# WanderDrive_AbsEnc.net
KiCad netlist of a schematic drawn in Altium Designer
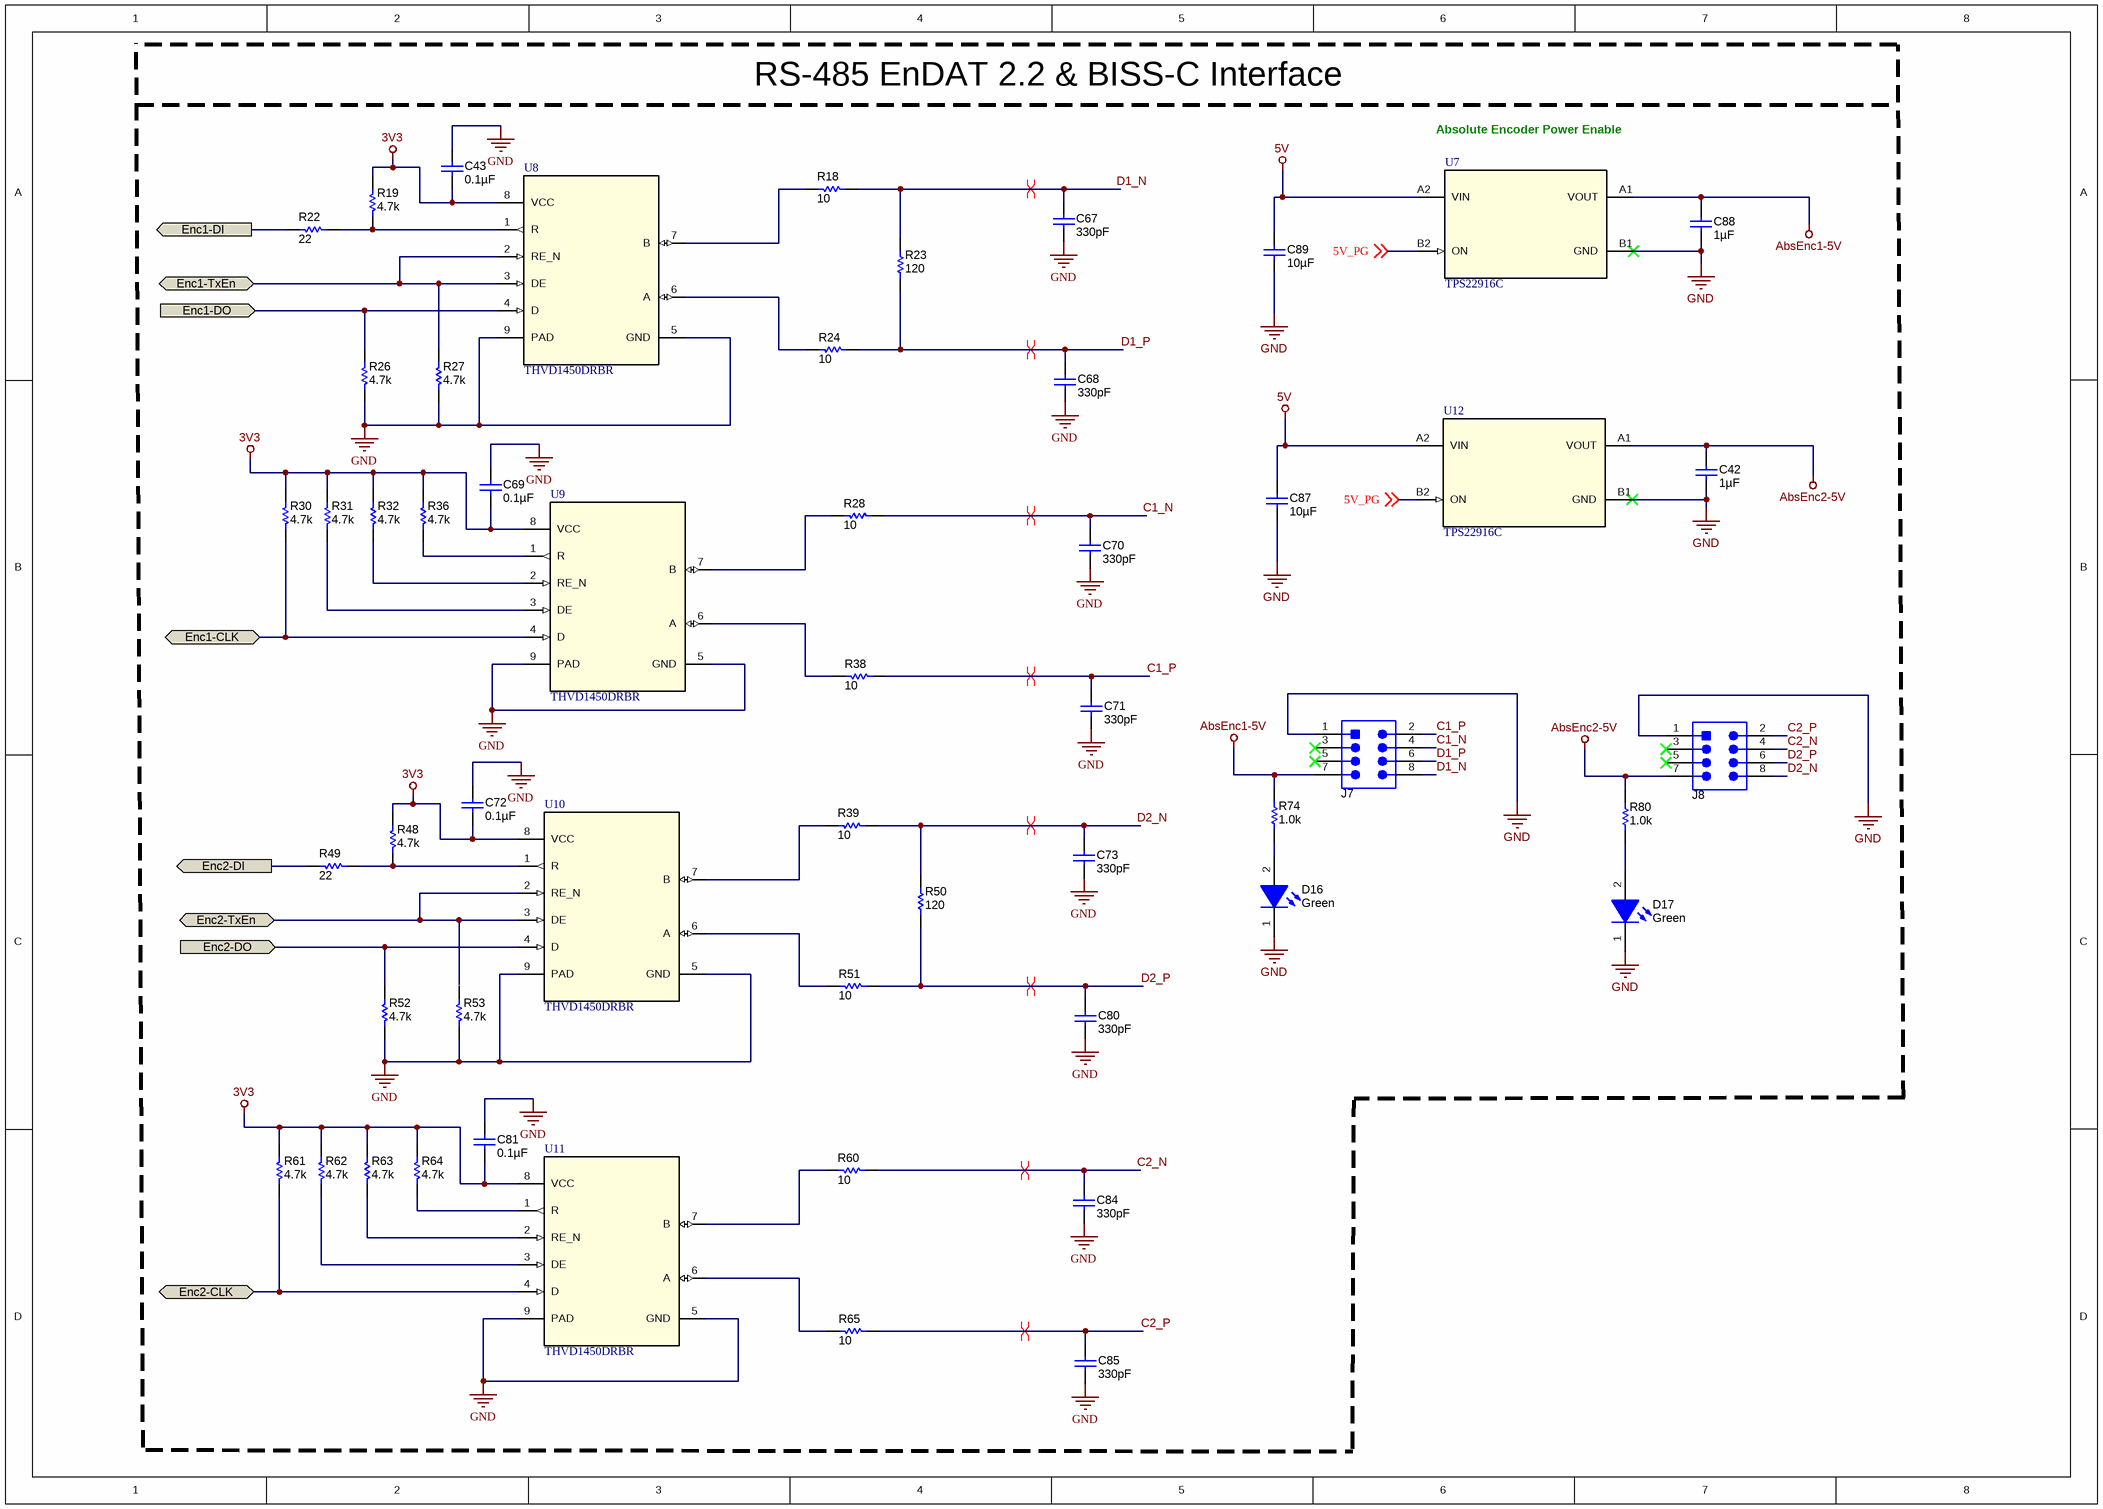
[diagram p0: WanderDrive_AbsEnc.SchDoc]

(export (version "E")
  (design (tool "Eeschema 10.0.6"))
  (components
    (comp (ref "C42")
      (value "TMK212BJ105KG-T")
      (footprint "0805_HV")
      (description "CAP, CERM, 1 µF, 20 V, +/- 10%, X5R, 0805")
      (fields
        (field (name "VALUEDISPLAYED") "1µF")
        (field (name "MANUFACTURER") "Taiyo Yuden")
        (field (name "PUBLISHER") "Texas Instruments")
      )
      (libsource (lib "Capacitor_Ceramic") (part "TMK212BJ105KG-T"))
    )
    (comp (ref "C43")
      (value "06033D104KAT2A")
      (footprint "0603")
      (description "CAP, CERM, 0.1uF, 25V, +/-10%, X5R, 0603")
      (fields
        (field (name "VALUEDISPLAYED") "0.1µF")
        (field (name "MANUFACTURER") "AVX")
        (field (name "PUBLISHER") "Texas Instruments")
      )
      (libsource (lib "Capacitor_Ceramic") (part "06033D104KAT2A"))
    )
    (comp (ref "C67")
      (value "GRM188R71H331KA01D")
      (footprint "0603")
      (description "CAP, CERM, 330pF, 50V, +/-10%, X7R, 0603")
      (fields
        (field (name "VALUEDISPLAYED") "330pF")
        (field (name "MANUFACTURER") "MuRata")
        (field (name "PUBLISHER") "Texas Instruments")
      )
      (libsource (lib "Capacitor_Ceramic") (part "GRM188R71H331KA01D"))
    )
    (comp (ref "C68")
      (value "GRM188R71H331KA01D")
      (footprint "0603")
      (description "CAP, CERM, 330pF, 50V, +/-10%, X7R, 0603")
      (fields
        (field (name "VALUEDISPLAYED") "330pF")
        (field (name "MANUFACTURER") "MuRata")
        (field (name "PUBLISHER") "Texas Instruments")
      )
      (libsource (lib "Capacitor_Ceramic") (part "GRM188R71H331KA01D"))
    )
    (comp (ref "C69")
      (value "06033D104KAT2A")
      (footprint "0603")
      (description "CAP, CERM, 0.1uF, 25V, +/-10%, X5R, 0603")
      (fields
        (field (name "VALUEDISPLAYED") "0.1µF")
        (field (name "MANUFACTURER") "AVX")
        (field (name "PUBLISHER") "Texas Instruments")
      )
      (libsource (lib "Capacitor_Ceramic") (part "06033D104KAT2A"))
    )
    (comp (ref "C70")
      (value "GRM188R71H331KA01D")
      (footprint "0603")
      (description "CAP, CERM, 330pF, 50V, +/-10%, X7R, 0603")
      (fields
        (field (name "VALUEDISPLAYED") "330pF")
        (field (name "MANUFACTURER") "MuRata")
        (field (name "PUBLISHER") "Texas Instruments")
      )
      (libsource (lib "Capacitor_Ceramic") (part "GRM188R71H331KA01D"))
    )
    (comp (ref "C71")
      (value "GRM188R71H331KA01D")
      (footprint "0603")
      (description "CAP, CERM, 330pF, 50V, +/-10%, X7R, 0603")
      (fields
        (field (name "VALUEDISPLAYED") "330pF")
        (field (name "MANUFACTURER") "MuRata")
        (field (name "PUBLISHER") "Texas Instruments")
      )
      (libsource (lib "Capacitor_Ceramic") (part "GRM188R71H331KA01D"))
    )
    (comp (ref "C72")
      (value "06033D104KAT2A")
      (footprint "0603")
      (description "CAP, CERM, 0.1uF, 25V, +/-10%, X5R, 0603")
      (fields
        (field (name "VALUEDISPLAYED") "0.1µF")
        (field (name "MANUFACTURER") "AVX")
        (field (name "PUBLISHER") "Texas Instruments")
      )
      (libsource (lib "Capacitor_Ceramic") (part "06033D104KAT2A"))
    )
    (comp (ref "C73")
      (value "GRM188R71H331KA01D")
      (footprint "0603")
      (description "CAP, CERM, 330pF, 50V, +/-10%, X7R, 0603")
      (fields
        (field (name "VALUEDISPLAYED") "330pF")
        (field (name "MANUFACTURER") "MuRata")
        (field (name "PUBLISHER") "Texas Instruments")
      )
      (libsource (lib "Capacitor_Ceramic") (part "GRM188R71H331KA01D"))
    )
    (comp (ref "C80")
      (value "GRM188R71H331KA01D")
      (footprint "0603")
      (description "CAP, CERM, 330pF, 50V, +/-10%, X7R, 0603")
      (fields
        (field (name "VALUEDISPLAYED") "330pF")
        (field (name "MANUFACTURER") "MuRata")
        (field (name "PUBLISHER") "Texas Instruments")
      )
      (libsource (lib "Capacitor_Ceramic") (part "GRM188R71H331KA01D"))
    )
    (comp (ref "C81")
      (value "06033D104KAT2A")
      (footprint "0603")
      (description "CAP, CERM, 0.1uF, 25V, +/-10%, X5R, 0603")
      (fields
        (field (name "VALUEDISPLAYED") "0.1µF")
        (field (name "MANUFACTURER") "AVX")
        (field (name "PUBLISHER") "Texas Instruments")
      )
      (libsource (lib "Capacitor_Ceramic") (part "06033D104KAT2A"))
    )
    (comp (ref "C84")
      (value "GRM188R71H331KA01D")
      (footprint "0603")
      (description "CAP, CERM, 330pF, 50V, +/-10%, X7R, 0603")
      (fields
        (field (name "VALUEDISPLAYED") "330pF")
        (field (name "MANUFACTURER") "MuRata")
        (field (name "PUBLISHER") "Texas Instruments")
      )
      (libsource (lib "Capacitor_Ceramic") (part "GRM188R71H331KA01D"))
    )
    (comp (ref "C85")
      (value "GRM188R71H331KA01D")
      (footprint "0603")
      (description "CAP, CERM, 330pF, 50V, +/-10%, X7R, 0603")
      (fields
        (field (name "VALUEDISPLAYED") "330pF")
        (field (name "MANUFACTURER") "MuRata")
        (field (name "PUBLISHER") "Texas Instruments")
      )
      (libsource (lib "Capacitor_Ceramic") (part "GRM188R71H331KA01D"))
    )
    (comp (ref "C87")
      (value "GRM21BR61E106KA73L")
      (footprint "0805_HV")
      (description "CAP, CERM, 10 µF, 25 V,+/- 10%, X5R, 0805")
      (fields
        (field (name "VALUEDISPLAYED") "10µF")
        (field (name "MANUFACTURER") "MuRata")
        (field (name "PUBLISHER") "Texas Instruments")
      )
      (libsource (lib "Capacitor_Ceramic") (part "GRM21BR61E106KA73L"))
    )
    (comp (ref "C88")
      (value "TMK212BJ105KG-T")
      (footprint "0805_HV")
      (description "CAP, CERM, 1 µF, 20 V, +/- 10%, X5R, 0805")
      (fields
        (field (name "VALUEDISPLAYED") "1µF")
        (field (name "MANUFACTURER") "Taiyo Yuden")
        (field (name "PUBLISHER") "Texas Instruments")
      )
      (libsource (lib "Capacitor_Ceramic") (part "TMK212BJ105KG-T"))
    )
    (comp (ref "C89")
      (value "GRM21BR61E106KA73L")
      (footprint "0805_HV")
      (description "CAP, CERM, 10 µF, 25 V,+/- 10%, X5R, 0805")
      (fields
        (field (name "VALUEDISPLAYED") "10µF")
        (field (name "MANUFACTURER") "MuRata")
        (field (name "PUBLISHER") "Texas Instruments")
      )
      (libsource (lib "Capacitor_Ceramic") (part "GRM21BR61E106KA73L"))
    )
    (comp (ref "D16")
      (value "Green")
      (footprint "WL-SMCW_GREEN")
      (description "LED, Green, SMD")
      (fields
        (field (name "MANUFACTURER") "Wurth Elektronik")
        (field (name "PARTNUMBER") "150060GS75000")
        (field (name "PUBLISHER") "Texas Instruments")
      )
      (libsource (lib "LED") (part "150060GS75000"))
    )
    (comp (ref "D17")
      (value "Green")
      (footprint "WL-SMCW_GREEN")
      (description "LED, Green, SMD")
      (fields
        (field (name "MANUFACTURER") "Wurth Elektronik")
        (field (name "PARTNUMBER") "150060GS75000")
        (field (name "PUBLISHER") "Texas Instruments")
      )
      (libsource (lib "LED") (part "150060GS75000"))
    )
    (comp (ref "J7")
      (value "70246-0801")
      (footprint "Molex_70246-0801")
      (description "Header(shrouded), 2.54mm, 4x2, Gold, TH")
      (fields
        (field (name "MANUFACTURER") "Molex")
        (field (name "SYMBOLCREATOR") "a0411947")
        (field (name "PUBLISHER") "Texas Instruments")
      )
      (libsource (lib "Connectors_Molex") (part "70246-0801"))
    )
    (comp (ref "J8")
      (value "70246-0801")
      (footprint "Molex_70246-0801")
      (description "Header(shrouded), 2.54mm, 4x2, Gold, TH")
      (fields
        (field (name "MANUFACTURER") "Molex")
        (field (name "SYMBOLCREATOR") "a0411947")
        (field (name "PUBLISHER") "Texas Instruments")
      )
      (libsource (lib "Connectors_Molex") (part "70246-0801"))
    )
    (comp (ref "R18")
      (value "10")
      (footprint "0603")
      (description "RES, 10 ohm, 5%, 0.25W, 0603")
      (fields
        (field (name "PARTNUMBER") "CRCW060310R0JNEAHP")
        (field (name "MANUFACTURER") "Vishay-Dale")
        (field (name "PUBLISHER") "Texas Instruments")
      )
      (libsource (lib "Resistor_0603") (part "CRCW060310R0JNEAHP"))
    )
    (comp (ref "R19")
      (value "4.7k")
      (footprint "0603")
      (description "RES, 4.7k ohm, 5%, 0.1W, 0603")
      (fields
        (field (name "PARTNUMBER") "CRCW06034K70JNEA")
        (field (name "MANUFACTURER") "Vishay-Dale")
        (field (name "PUBLISHER") "Texas Instruments")
      )
      (libsource (lib "Resistor_0603") (part "CRCW06034K70JNEA"))
    )
    (comp (ref "R22")
      (value "22")
      (footprint "0603")
      (description "RES, 22 ohm, 5%, 0.1W, 0603")
      (fields
        (field (name "PARTNUMBER") "CRCW060322R0JNEA")
        (field (name "MANUFACTURER") "Vishay-Dale")
        (field (name "PUBLISHER") "Texas Instruments")
      )
      (libsource (lib "Resistor_0603") (part "CRCW060322R0JNEA"))
    )
    (comp (ref "R23")
      (value "CRCW0603120RJNEA")
      (footprint "0603")
      (description "RES, 120, 5%, 0.1 W, 0603")
      (fields
        (field (name "VALUEDISPLAYED") "120")
        (field (name "MANUFACTURER") "Vishay-Dale")
        (field (name "PUBLISHER") "Texas Instruments")
      )
      (libsource (lib "Resistor_0603") (part "CRCW0603120RJNEA"))
    )
    (comp (ref "R24")
      (value "10")
      (footprint "0603")
      (description "RES, 10 ohm, 5%, 0.25W, 0603")
      (fields
        (field (name "PARTNUMBER") "CRCW060310R0JNEAHP")
        (field (name "MANUFACTURER") "Vishay-Dale")
        (field (name "PUBLISHER") "Texas Instruments")
      )
      (libsource (lib "Resistor_0603") (part "CRCW060310R0JNEAHP"))
    )
    (comp (ref "R26")
      (value "4.7k")
      (footprint "0603")
      (description "RES, 4.7k ohm, 5%, 0.1W, 0603")
      (fields
        (field (name "PARTNUMBER") "CRCW06034K70JNEA")
        (field (name "MANUFACTURER") "Vishay-Dale")
        (field (name "PUBLISHER") "Texas Instruments")
      )
      (libsource (lib "Resistor_0603") (part "CRCW06034K70JNEA"))
    )
    (comp (ref "R27")
      (value "4.7k")
      (footprint "0603")
      (description "RES, 4.7k ohm, 5%, 0.1W, 0603")
      (fields
        (field (name "PARTNUMBER") "CRCW06034K70JNEA")
        (field (name "MANUFACTURER") "Vishay-Dale")
        (field (name "PUBLISHER") "Texas Instruments")
      )
      (libsource (lib "Resistor_0603") (part "CRCW06034K70JNEA"))
    )
    (comp (ref "R28")
      (value "10")
      (footprint "0603")
      (description "RES, 10 ohm, 5%, 0.25W, 0603")
      (fields
        (field (name "PARTNUMBER") "CRCW060310R0JNEAHP")
        (field (name "MANUFACTURER") "Vishay-Dale")
        (field (name "PUBLISHER") "Texas Instruments")
      )
      (libsource (lib "Resistor_0603") (part "CRCW060310R0JNEAHP"))
    )
    (comp (ref "R30")
      (value "4.7k")
      (footprint "0603")
      (description "RES, 4.7k ohm, 5%, 0.1W, 0603")
      (fields
        (field (name "PARTNUMBER") "CRCW06034K70JNEA")
        (field (name "MANUFACTURER") "Vishay-Dale")
        (field (name "PUBLISHER") "Texas Instruments")
      )
      (libsource (lib "Resistor_0603") (part "CRCW06034K70JNEA"))
    )
    (comp (ref "R31")
      (value "4.7k")
      (footprint "0603")
      (description "RES, 4.7k ohm, 5%, 0.1W, 0603")
      (fields
        (field (name "PARTNUMBER") "CRCW06034K70JNEA")
        (field (name "MANUFACTURER") "Vishay-Dale")
        (field (name "PUBLISHER") "Texas Instruments")
      )
      (libsource (lib "Resistor_0603") (part "CRCW06034K70JNEA"))
    )
    (comp (ref "R32")
      (value "4.7k")
      (footprint "0603")
      (description "RES, 4.7k ohm, 5%, 0.1W, 0603")
      (fields
        (field (name "PARTNUMBER") "CRCW06034K70JNEA")
        (field (name "MANUFACTURER") "Vishay-Dale")
        (field (name "PUBLISHER") "Texas Instruments")
      )
      (libsource (lib "Resistor_0603") (part "CRCW06034K70JNEA"))
    )
    (comp (ref "R36")
      (value "4.7k")
      (footprint "0603")
      (description "RES, 4.7k ohm, 5%, 0.1W, 0603")
      (fields
        (field (name "PARTNUMBER") "CRCW06034K70JNEA")
        (field (name "MANUFACTURER") "Vishay-Dale")
        (field (name "PUBLISHER") "Texas Instruments")
      )
      (libsource (lib "Resistor_0603") (part "CRCW06034K70JNEA"))
    )
    (comp (ref "R38")
      (value "10")
      (footprint "0603")
      (description "RES, 10 ohm, 5%, 0.25W, 0603")
      (fields
        (field (name "PARTNUMBER") "CRCW060310R0JNEAHP")
        (field (name "MANUFACTURER") "Vishay-Dale")
        (field (name "PUBLISHER") "Texas Instruments")
      )
      (libsource (lib "Resistor_0603") (part "CRCW060310R0JNEAHP"))
    )
    (comp (ref "R39")
      (value "10")
      (footprint "0603")
      (description "RES, 10 ohm, 5%, 0.25W, 0603")
      (fields
        (field (name "PARTNUMBER") "CRCW060310R0JNEAHP")
        (field (name "MANUFACTURER") "Vishay-Dale")
        (field (name "PUBLISHER") "Texas Instruments")
      )
      (libsource (lib "Resistor_0603") (part "CRCW060310R0JNEAHP"))
    )
    (comp (ref "R48")
      (value "4.7k")
      (footprint "0603")
      (description "RES, 4.7k ohm, 5%, 0.1W, 0603")
      (fields
        (field (name "PARTNUMBER") "CRCW06034K70JNEA")
        (field (name "MANUFACTURER") "Vishay-Dale")
        (field (name "PUBLISHER") "Texas Instruments")
      )
      (libsource (lib "Resistor_0603") (part "CRCW06034K70JNEA"))
    )
    (comp (ref "R49")
      (value "22")
      (footprint "0603")
      (description "RES, 22 ohm, 5%, 0.1W, 0603")
      (fields
        (field (name "PARTNUMBER") "CRCW060322R0JNEA")
        (field (name "MANUFACTURER") "Vishay-Dale")
        (field (name "PUBLISHER") "Texas Instruments")
      )
      (libsource (lib "Resistor_0603") (part "CRCW060322R0JNEA"))
    )
    (comp (ref "R50")
      (value "CRCW0603120RJNEA")
      (footprint "0603")
      (description "RES, 120, 5%, 0.1 W, 0603")
      (fields
        (field (name "VALUEDISPLAYED") "120")
        (field (name "MANUFACTURER") "Vishay-Dale")
        (field (name "PUBLISHER") "Texas Instruments")
      )
      (libsource (lib "Resistor_0603") (part "CRCW0603120RJNEA"))
    )
    (comp (ref "R51")
      (value "10")
      (footprint "0603")
      (description "RES, 10 ohm, 5%, 0.25W, 0603")
      (fields
        (field (name "PARTNUMBER") "CRCW060310R0JNEAHP")
        (field (name "MANUFACTURER") "Vishay-Dale")
        (field (name "PUBLISHER") "Texas Instruments")
      )
      (libsource (lib "Resistor_0603") (part "CRCW060310R0JNEAHP"))
    )
    (comp (ref "R52")
      (value "4.7k")
      (footprint "0603")
      (description "RES, 4.7k ohm, 5%, 0.1W, 0603")
      (fields
        (field (name "PARTNUMBER") "CRCW06034K70JNEA")
        (field (name "MANUFACTURER") "Vishay-Dale")
        (field (name "PUBLISHER") "Texas Instruments")
      )
      (libsource (lib "Resistor_0603") (part "CRCW06034K70JNEA"))
    )
    (comp (ref "R53")
      (value "4.7k")
      (footprint "0603")
      (description "RES, 4.7k ohm, 5%, 0.1W, 0603")
      (fields
        (field (name "PARTNUMBER") "CRCW06034K70JNEA")
        (field (name "MANUFACTURER") "Vishay-Dale")
        (field (name "PUBLISHER") "Texas Instruments")
      )
      (libsource (lib "Resistor_0603") (part "CRCW06034K70JNEA"))
    )
    (comp (ref "R60")
      (value "10")
      (footprint "0603")
      (description "RES, 10 ohm, 5%, 0.25W, 0603")
      (fields
        (field (name "PARTNUMBER") "CRCW060310R0JNEAHP")
        (field (name "MANUFACTURER") "Vishay-Dale")
        (field (name "PUBLISHER") "Texas Instruments")
      )
      (libsource (lib "Resistor_0603") (part "CRCW060310R0JNEAHP"))
    )
    (comp (ref "R61")
      (value "4.7k")
      (footprint "0603")
      (description "RES, 4.7k ohm, 5%, 0.1W, 0603")
      (fields
        (field (name "PARTNUMBER") "CRCW06034K70JNEA")
        (field (name "MANUFACTURER") "Vishay-Dale")
        (field (name "PUBLISHER") "Texas Instruments")
      )
      (libsource (lib "Resistor_0603") (part "CRCW06034K70JNEA"))
    )
    (comp (ref "R62")
      (value "4.7k")
      (footprint "0603")
      (description "RES, 4.7k ohm, 5%, 0.1W, 0603")
      (fields
        (field (name "PARTNUMBER") "CRCW06034K70JNEA")
        (field (name "MANUFACTURER") "Vishay-Dale")
        (field (name "PUBLISHER") "Texas Instruments")
      )
      (libsource (lib "Resistor_0603") (part "CRCW06034K70JNEA"))
    )
    (comp (ref "R63")
      (value "4.7k")
      (footprint "0603")
      (description "RES, 4.7k ohm, 5%, 0.1W, 0603")
      (fields
        (field (name "PARTNUMBER") "CRCW06034K70JNEA")
        (field (name "MANUFACTURER") "Vishay-Dale")
        (field (name "PUBLISHER") "Texas Instruments")
      )
      (libsource (lib "Resistor_0603") (part "CRCW06034K70JNEA"))
    )
    (comp (ref "R64")
      (value "4.7k")
      (footprint "0603")
      (description "RES, 4.7k ohm, 5%, 0.1W, 0603")
      (fields
        (field (name "PARTNUMBER") "CRCW06034K70JNEA")
        (field (name "MANUFACTURER") "Vishay-Dale")
        (field (name "PUBLISHER") "Texas Instruments")
      )
      (libsource (lib "Resistor_0603") (part "CRCW06034K70JNEA"))
    )
    (comp (ref "R65")
      (value "10")
      (footprint "0603")
      (description "RES, 10 ohm, 5%, 0.25W, 0603")
      (fields
        (field (name "PARTNUMBER") "CRCW060310R0JNEAHP")
        (field (name "MANUFACTURER") "Vishay-Dale")
        (field (name "PUBLISHER") "Texas Instruments")
      )
      (libsource (lib "Resistor_0603") (part "CRCW060310R0JNEAHP"))
    )
    (comp (ref "R74")
      (value "CRCW04021K00JNED")
      (footprint "0402")
      (description "RES, 1.0 k, 5%, 0.063 W, 0402")
      (fields
        (field (name "VALUEDISPLAYED") "1.0k")
        (field (name "MANUFACTURER") "Vishay-Dale")
        (field (name "PUBLISHER") "Texas Instruments")
      )
      (libsource (lib "Resistor_0402") (part "CRCW04021K00JNED"))
    )
    (comp (ref "R80")
      (value "CRCW04021K00JNED")
      (footprint "0402")
      (description "RES, 1.0 k, 5%, 0.063 W, 0402")
      (fields
        (field (name "VALUEDISPLAYED") "1.0k")
        (field (name "MANUFACTURER") "Vishay-Dale")
        (field (name "PUBLISHER") "Texas Instruments")
      )
      (libsource (lib "Resistor_0402") (part "CRCW04021K00JNED"))
    )
    (comp (ref "U7")
      (value "TPS22916C")
      (footprint "YFP0004ABAB")
      (description "TPS22916CY Single-Channel Ultra-Low Leakage Load Switch 2A 60 mO 1V to 5.5V 4-Pin DSBGA T/R")
      (fields
        (field (name "MANUFACTURER") "Texas Instruments")
        (field (name "MANUFACTURER PART NUMBER") "TPS22916CYFPR")
      )
      (libsource (lib "Altium_TPS") (part "TPS22916C"))
    )
    (comp (ref "U8")
      (value "THVD1450DRBR")
      (footprint "DRB0008F")
      (fields (field (name "MANUFACTURER") "Texas Instruments"))
      (libsource (lib "Texas_Instrumented") (part "THVD1450DRBR"))
    )
    (comp (ref "U9")
      (value "THVD1450DRBR")
      (footprint "DRB0008F")
      (fields (field (name "MANUFACTURER") "Texas Instruments"))
      (libsource (lib "Texas_Instrumented") (part "THVD1450DRBR"))
    )
    (comp (ref "U10")
      (value "THVD1450DRBR")
      (footprint "DRB0008F")
      (fields (field (name "MANUFACTURER") "Texas Instruments"))
      (libsource (lib "Texas_Instrumented") (part "THVD1450DRBR"))
    )
    (comp (ref "U11")
      (value "THVD1450DRBR")
      (footprint "DRB0008F")
      (fields (field (name "MANUFACTURER") "Texas Instruments"))
      (libsource (lib "Texas_Instrumented") (part "THVD1450DRBR"))
    )
    (comp (ref "U12")
      (value "TPS22916C")
      (footprint "YFP0004ABAB")
      (description "TPS22916CY Single-Channel Ultra-Low Leakage Load Switch 2A 60 mO 1V to 5.5V 4-Pin DSBGA T/R")
      (fields
        (field (name "MANUFACTURER") "Texas Instruments")
        (field (name "MANUFACTURER PART NUMBER") "TPS22916CYFPR")
      )
      (libsource (lib "Altium_TPS") (part "TPS22916C"))
    )
  )
  (nets
    (net (code "1") (name "/C1_N") (class "Default")
      (node (ref "C70") (pin "2") (pinfunction "2_2") (pintype "passive"))
      (node (ref "J7") (pin "4") (pinfunction "4_4") (pintype "passive"))
      (node (ref "R28") (pin "1") (pinfunction "1_1") (pintype "passive"))
    )
    (net (code "2") (name "/C1_P") (class "Default")
      (node (ref "C71") (pin "1") (pinfunction "1_1") (pintype "passive"))
      (node (ref "J7") (pin "2") (pinfunction "2_2") (pintype "passive"))
      (node (ref "R38") (pin "1") (pinfunction "1_1") (pintype "passive"))
    )
    (net (code "3") (name "/C2_N") (class "Default")
      (node (ref "C84") (pin "2") (pinfunction "2_2") (pintype "passive"))
      (node (ref "J8") (pin "4") (pinfunction "4_4") (pintype "passive"))
      (node (ref "R60") (pin "1") (pinfunction "1_1") (pintype "passive"))
    )
    (net (code "4") (name "/C2_P") (class "Default")
      (node (ref "C85") (pin "1") (pinfunction "1_1") (pintype "passive"))
      (node (ref "J8") (pin "2") (pinfunction "2_2") (pintype "passive"))
      (node (ref "R65") (pin "1") (pinfunction "1_1") (pintype "passive"))
    )
    (net (code "5") (name "/D1_N") (class "Default")
      (node (ref "C67") (pin "2") (pinfunction "2_2") (pintype "passive"))
      (node (ref "J7") (pin "8") (pinfunction "8_8") (pintype "passive"))
      (node (ref "R18") (pin "1") (pinfunction "1_1") (pintype "passive"))
      (node (ref "R23") (pin "2") (pinfunction "2_2") (pintype "passive"))
    )
    (net (code "6") (name "/D1_P") (class "Default")
      (node (ref "C68") (pin "1") (pinfunction "1_1") (pintype "passive"))
      (node (ref "J7") (pin "6") (pinfunction "6_6") (pintype "passive"))
      (node (ref "R23") (pin "1") (pinfunction "1_1") (pintype "passive"))
      (node (ref "R24") (pin "1") (pinfunction "1_1") (pintype "passive"))
    )
    (net (code "7") (name "/D2_N") (class "Default")
      (node (ref "C73") (pin "2") (pinfunction "2_2") (pintype "passive"))
      (node (ref "J8") (pin "8") (pinfunction "8_8") (pintype "passive"))
      (node (ref "R39") (pin "1") (pinfunction "1_1") (pintype "passive"))
      (node (ref "R50") (pin "2") (pinfunction "2_2") (pintype "passive"))
    )
    (net (code "8") (name "/D2_P") (class "Default")
      (node (ref "C80") (pin "1") (pinfunction "1_1") (pintype "passive"))
      (node (ref "J8") (pin "6") (pinfunction "6_6") (pintype "passive"))
      (node (ref "R50") (pin "1") (pinfunction "1_1") (pintype "passive"))
      (node (ref "R51") (pin "1") (pinfunction "1_1") (pintype "passive"))
    )
    (net (code "9") (name "/Enc1-CLK") (class "Default")
      (node (ref "R30") (pin "2") (pinfunction "2_2") (pintype "passive"))
      (node (ref "U9") (pin "4") (pinfunction "D_4") (pintype "input"))
    )
    (net (code "10") (name "/Enc1-DI") (class "Default")
      (node (ref "R22") (pin "2") (pinfunction "2_2") (pintype "passive"))
    )
    (net (code "11") (name "/Enc1-DO") (class "Default")
      (node (ref "R26") (pin "1") (pinfunction "1_1") (pintype "passive"))
      (node (ref "U8") (pin "4") (pinfunction "D_4") (pintype "input"))
    )
    (net (code "12") (name "/Enc1-TxEn") (class "Default")
      (node (ref "U8") (pin "2") (pinfunction "RE_N_2") (pintype "input"))
      (node (ref "U8") (pin "3") (pinfunction "DE_3") (pintype "input"))
    )
    (net (code "13") (name "/Enc2-CLK") (class "Default")
      (node (ref "R61") (pin "2") (pinfunction "2_2") (pintype "passive"))
      (node (ref "U11") (pin "4") (pinfunction "D_4") (pintype "input"))
    )
    (net (code "14") (name "/Enc2-DI") (class "Default")
      (node (ref "R49") (pin "2") (pinfunction "2_2") (pintype "passive"))
    )
    (net (code "15") (name "/Enc2-DO") (class "Default")
      (node (ref "R52") (pin "1") (pinfunction "1_1") (pintype "passive"))
      (node (ref "U10") (pin "4") (pinfunction "D_4") (pintype "input"))
    )
    (net (code "16") (name "/Enc2-TxEn") (class "Default")
      (node (ref "U10") (pin "2") (pinfunction "RE_N_2") (pintype "input"))
      (node (ref "U10") (pin "3") (pinfunction "DE_3") (pintype "input"))
    )
    (net (code "17") (name "3V3") (class "Default")
      (node (ref "C43") (pin "1") (pinfunction "1_1") (pintype "passive"))
      (node (ref "C69") (pin "1") (pinfunction "1_1") (pintype "passive"))
      (node (ref "C72") (pin "1") (pinfunction "1_1") (pintype "passive"))
      (node (ref "C81") (pin "1") (pinfunction "1_1") (pintype "passive"))
      (node (ref "R19") (pin "2") (pinfunction "2_2") (pintype "passive"))
      (node (ref "R30") (pin "1") (pinfunction "1_1") (pintype "passive"))
      (node (ref "R31") (pin "1") (pinfunction "1_1") (pintype "passive"))
      (node (ref "R32") (pin "1") (pinfunction "1_1") (pintype "passive"))
      (node (ref "R36") (pin "1") (pinfunction "1_1") (pintype "passive"))
      (node (ref "R48") (pin "2") (pinfunction "2_2") (pintype "passive"))
      (node (ref "R61") (pin "1") (pinfunction "1_1") (pintype "passive"))
      (node (ref "R62") (pin "1") (pinfunction "1_1") (pintype "passive"))
      (node (ref "R63") (pin "1") (pinfunction "1_1") (pintype "passive"))
      (node (ref "R64") (pin "1") (pinfunction "1_1") (pintype "passive"))
      (node (ref "U10") (pin "8") (pinfunction "VCC_8") (pintype "power_in"))
      (node (ref "U11") (pin "8") (pinfunction "VCC_8") (pintype "power_in"))
      (node (ref "U8") (pin "8") (pinfunction "VCC_8") (pintype "power_in"))
      (node (ref "U9") (pin "8") (pinfunction "VCC_8") (pintype "power_in"))
    )
    (net (code "18") (name "5V") (class "Default")
      (node (ref "C87") (pin "1") (pinfunction "1_1") (pintype "passive"))
      (node (ref "C89") (pin "1") (pinfunction "1_1") (pintype "passive"))
      (node (ref "U12") (pin "A2") (pinfunction "VIN_A2") (pintype "power_in"))
      (node (ref "U7") (pin "A2") (pinfunction "VIN_A2") (pintype "power_in"))
    )
    (net (code "19") (name "5V_PG") (class "Default")
      (node (ref "U12") (pin "B2") (pinfunction "ON_B2") (pintype "input"))
      (node (ref "U7") (pin "B2") (pinfunction "ON_B2") (pintype "input"))
    )
    (net (code "20") (name "AbsEnc1-5V") (class "Default")
      (node (ref "C88") (pin "1") (pinfunction "1_1") (pintype "passive"))
      (node (ref "J7") (pin "7") (pinfunction "7_7") (pintype "passive"))
      (node (ref "R74") (pin "2") (pinfunction "2_2") (pintype "passive"))
      (node (ref "U7") (pin "A1") (pinfunction "VOUT_A1") (pintype "power_in"))
    )
    (net (code "21") (name "AbsEnc2-5V") (class "Default")
      (node (ref "C42") (pin "1") (pinfunction "1_1") (pintype "passive"))
      (node (ref "J8") (pin "7") (pinfunction "7_7") (pintype "passive"))
      (node (ref "R80") (pin "2") (pinfunction "2_2") (pintype "passive"))
      (node (ref "U12") (pin "A1") (pinfunction "VOUT_A1") (pintype "power_in"))
    )
    (net (code "22") (name "GND") (class "Default")
      (node (ref "C42") (pin "2") (pinfunction "2_2") (pintype "passive"))
      (node (ref "C43") (pin "2") (pinfunction "2_2") (pintype "passive"))
      (node (ref "C67") (pin "1") (pinfunction "1_1") (pintype "passive"))
      (node (ref "C68") (pin "2") (pinfunction "2_2") (pintype "passive"))
      (node (ref "C69") (pin "2") (pinfunction "2_2") (pintype "passive"))
      (node (ref "C70") (pin "1") (pinfunction "1_1") (pintype "passive"))
      (node (ref "C71") (pin "2") (pinfunction "2_2") (pintype "passive"))
      (node (ref "C72") (pin "2") (pinfunction "2_2") (pintype "passive"))
      (node (ref "C73") (pin "1") (pinfunction "1_1") (pintype "passive"))
      (node (ref "C80") (pin "2") (pinfunction "2_2") (pintype "passive"))
      (node (ref "C81") (pin "2") (pinfunction "2_2") (pintype "passive"))
      (node (ref "C84") (pin "1") (pinfunction "1_1") (pintype "passive"))
      (node (ref "C85") (pin "2") (pinfunction "2_2") (pintype "passive"))
      (node (ref "C87") (pin "2") (pinfunction "2_2") (pintype "passive"))
      (node (ref "C88") (pin "2") (pinfunction "2_2") (pintype "passive"))
      (node (ref "C89") (pin "2") (pinfunction "2_2") (pintype "passive"))
      (node (ref "D16") (pin "1") (pinfunction "K_1") (pintype "passive"))
      (node (ref "D17") (pin "1") (pinfunction "K_1") (pintype "passive"))
      (node (ref "J7") (pin "1") (pinfunction "1_1") (pintype "passive"))
      (node (ref "J8") (pin "1") (pinfunction "1_1") (pintype "passive"))
      (node (ref "R26") (pin "2") (pinfunction "2_2") (pintype "passive"))
      (node (ref "R27") (pin "2") (pinfunction "2_2") (pintype "passive"))
      (node (ref "R52") (pin "2") (pinfunction "2_2") (pintype "passive"))
      (node (ref "R53") (pin "2") (pinfunction "2_2") (pintype "passive"))
      (node (ref "U10") (pin "5") (pinfunction "GND_5") (pintype "power_in"))
      (node (ref "U10") (pin "9") (pinfunction "PAD_9") (pintype "passive"))
      (node (ref "U11") (pin "5") (pinfunction "GND_5") (pintype "power_in"))
      (node (ref "U11") (pin "9") (pinfunction "PAD_9") (pintype "passive"))
      (node (ref "U12") (pin "B1") (pinfunction "GND_B1") (pintype "power_in"))
      (node (ref "U7") (pin "B1") (pinfunction "GND_B1") (pintype "power_in"))
      (node (ref "U8") (pin "5") (pinfunction "GND_5") (pintype "power_in"))
      (node (ref "U8") (pin "9") (pinfunction "PAD_9") (pintype "passive"))
      (node (ref "U9") (pin "5") (pinfunction "GND_5") (pintype "power_in"))
      (node (ref "U9") (pin "9") (pinfunction "PAD_9") (pintype "passive"))
    )
    (net (code "23") (name "Net-(D16-A)") (class "Default")
      (node (ref "D16") (pin "2") (pinfunction "A_2") (pintype "passive"))
      (node (ref "R74") (pin "1") (pinfunction "1_1") (pintype "passive"))
    )
    (net (code "24") (name "Net-(D17-A)") (class "Default")
      (node (ref "D17") (pin "2") (pinfunction "A_2") (pintype "passive"))
      (node (ref "R80") (pin "1") (pinfunction "1_1") (pintype "passive"))
    )
    (net (code "25") (name "Net-(U8-A)") (class "Default")
      (node (ref "R24") (pin "2") (pinfunction "2_2") (pintype "passive"))
      (node (ref "U8") (pin "6") (pinfunction "A_6") (pintype "bidirectional"))
    )
    (net (code "26") (name "Net-(U8-B)") (class "Default")
      (node (ref "R18") (pin "2") (pinfunction "2_2") (pintype "passive"))
      (node (ref "U8") (pin "7") (pinfunction "B_7") (pintype "bidirectional"))
    )
    (net (code "27") (name "Net-(U8-R)") (class "Default")
      (node (ref "R19") (pin "1") (pinfunction "1_1") (pintype "passive"))
      (node (ref "R22") (pin "1") (pinfunction "1_1") (pintype "passive"))
      (node (ref "U8") (pin "1") (pinfunction "R_1") (pintype "output"))
    )
    (net (code "28") (name "Net-(U9-A)") (class "Default")
      (node (ref "R38") (pin "2") (pinfunction "2_2") (pintype "passive"))
      (node (ref "U9") (pin "6") (pinfunction "A_6") (pintype "bidirectional"))
    )
    (net (code "29") (name "Net-(U9-B)") (class "Default")
      (node (ref "R28") (pin "2") (pinfunction "2_2") (pintype "passive"))
      (node (ref "U9") (pin "7") (pinfunction "B_7") (pintype "bidirectional"))
    )
    (net (code "30") (name "Net-(U9-DE)") (class "Default")
      (node (ref "R31") (pin "2") (pinfunction "2_2") (pintype "passive"))
      (node (ref "U9") (pin "3") (pinfunction "DE_3") (pintype "input"))
    )
    (net (code "31") (name "Net-(U9-R)") (class "Default")
      (node (ref "R36") (pin "2") (pinfunction "2_2") (pintype "passive"))
      (node (ref "U9") (pin "1") (pinfunction "R_1") (pintype "output"))
    )
    (net (code "32") (name "Net-(U9-RE_N)") (class "Default")
      (node (ref "R32") (pin "2") (pinfunction "2_2") (pintype "passive"))
      (node (ref "U9") (pin "2") (pinfunction "RE_N_2") (pintype "input"))
    )
    (net (code "33") (name "Net-(U10-A)") (class "Default")
      (node (ref "R51") (pin "2") (pinfunction "2_2") (pintype "passive"))
      (node (ref "U10") (pin "6") (pinfunction "A_6") (pintype "bidirectional"))
    )
    (net (code "34") (name "Net-(U10-B)") (class "Default")
      (node (ref "R39") (pin "2") (pinfunction "2_2") (pintype "passive"))
      (node (ref "U10") (pin "7") (pinfunction "B_7") (pintype "bidirectional"))
    )
    (net (code "35") (name "Net-(U10-R)") (class "Default")
      (node (ref "R48") (pin "1") (pinfunction "1_1") (pintype "passive"))
      (node (ref "R49") (pin "1") (pinfunction "1_1") (pintype "passive"))
      (node (ref "U10") (pin "1") (pinfunction "R_1") (pintype "output"))
    )
    (net (code "36") (name "Net-(U11-A)") (class "Default")
      (node (ref "R65") (pin "2") (pinfunction "2_2") (pintype "passive"))
      (node (ref "U11") (pin "6") (pinfunction "A_6") (pintype "bidirectional"))
    )
    (net (code "37") (name "Net-(U11-B)") (class "Default")
      (node (ref "R60") (pin "2") (pinfunction "2_2") (pintype "passive"))
      (node (ref "U11") (pin "7") (pinfunction "B_7") (pintype "bidirectional"))
    )
    (net (code "38") (name "Net-(U11-DE)") (class "Default")
      (node (ref "R62") (pin "2") (pinfunction "2_2") (pintype "passive"))
      (node (ref "U11") (pin "3") (pinfunction "DE_3") (pintype "input"))
    )
    (net (code "39") (name "Net-(U11-R)") (class "Default")
      (node (ref "R64") (pin "2") (pinfunction "2_2") (pintype "passive"))
      (node (ref "U11") (pin "1") (pinfunction "R_1") (pintype "output"))
    )
    (net (code "40") (name "Net-(U11-RE_N)") (class "Default")
      (node (ref "R63") (pin "2") (pinfunction "2_2") (pintype "passive"))
      (node (ref "U11") (pin "2") (pinfunction "RE_N_2") (pintype "input"))
    )
    (net (code "41") (name "unconnected-(J7-Pad3)") (class "Default")
      (node (ref "J7") (pin "3") (pinfunction "3_3") (pintype "passive+no_connect"))
    )
    (net (code "42") (name "unconnected-(J7-Pad5)") (class "Default")
      (node (ref "J7") (pin "5") (pinfunction "5_5") (pintype "passive+no_connect"))
    )
    (net (code "43") (name "unconnected-(J8-Pad3)") (class "Default")
      (node (ref "J8") (pin "3") (pinfunction "3_3") (pintype "passive+no_connect"))
    )
    (net (code "44") (name "unconnected-(J8-Pad5)") (class "Default")
      (node (ref "J8") (pin "5") (pinfunction "5_5") (pintype "passive+no_connect"))
    )
    (net (code "45") (name "unconnected-(R27-Pad1)") (class "Default")
      (node (ref "R27") (pin "1") (pinfunction "1_1") (pintype "passive"))
    )
    (net (code "46") (name "unconnected-(R53-Pad1)") (class "Default")
      (node (ref "R53") (pin "1") (pinfunction "1_1") (pintype "passive"))
    )
  )
)
